# 07_LMS7002M_Power.net
KiCad netlist of a schematic drawn in Altium Designer
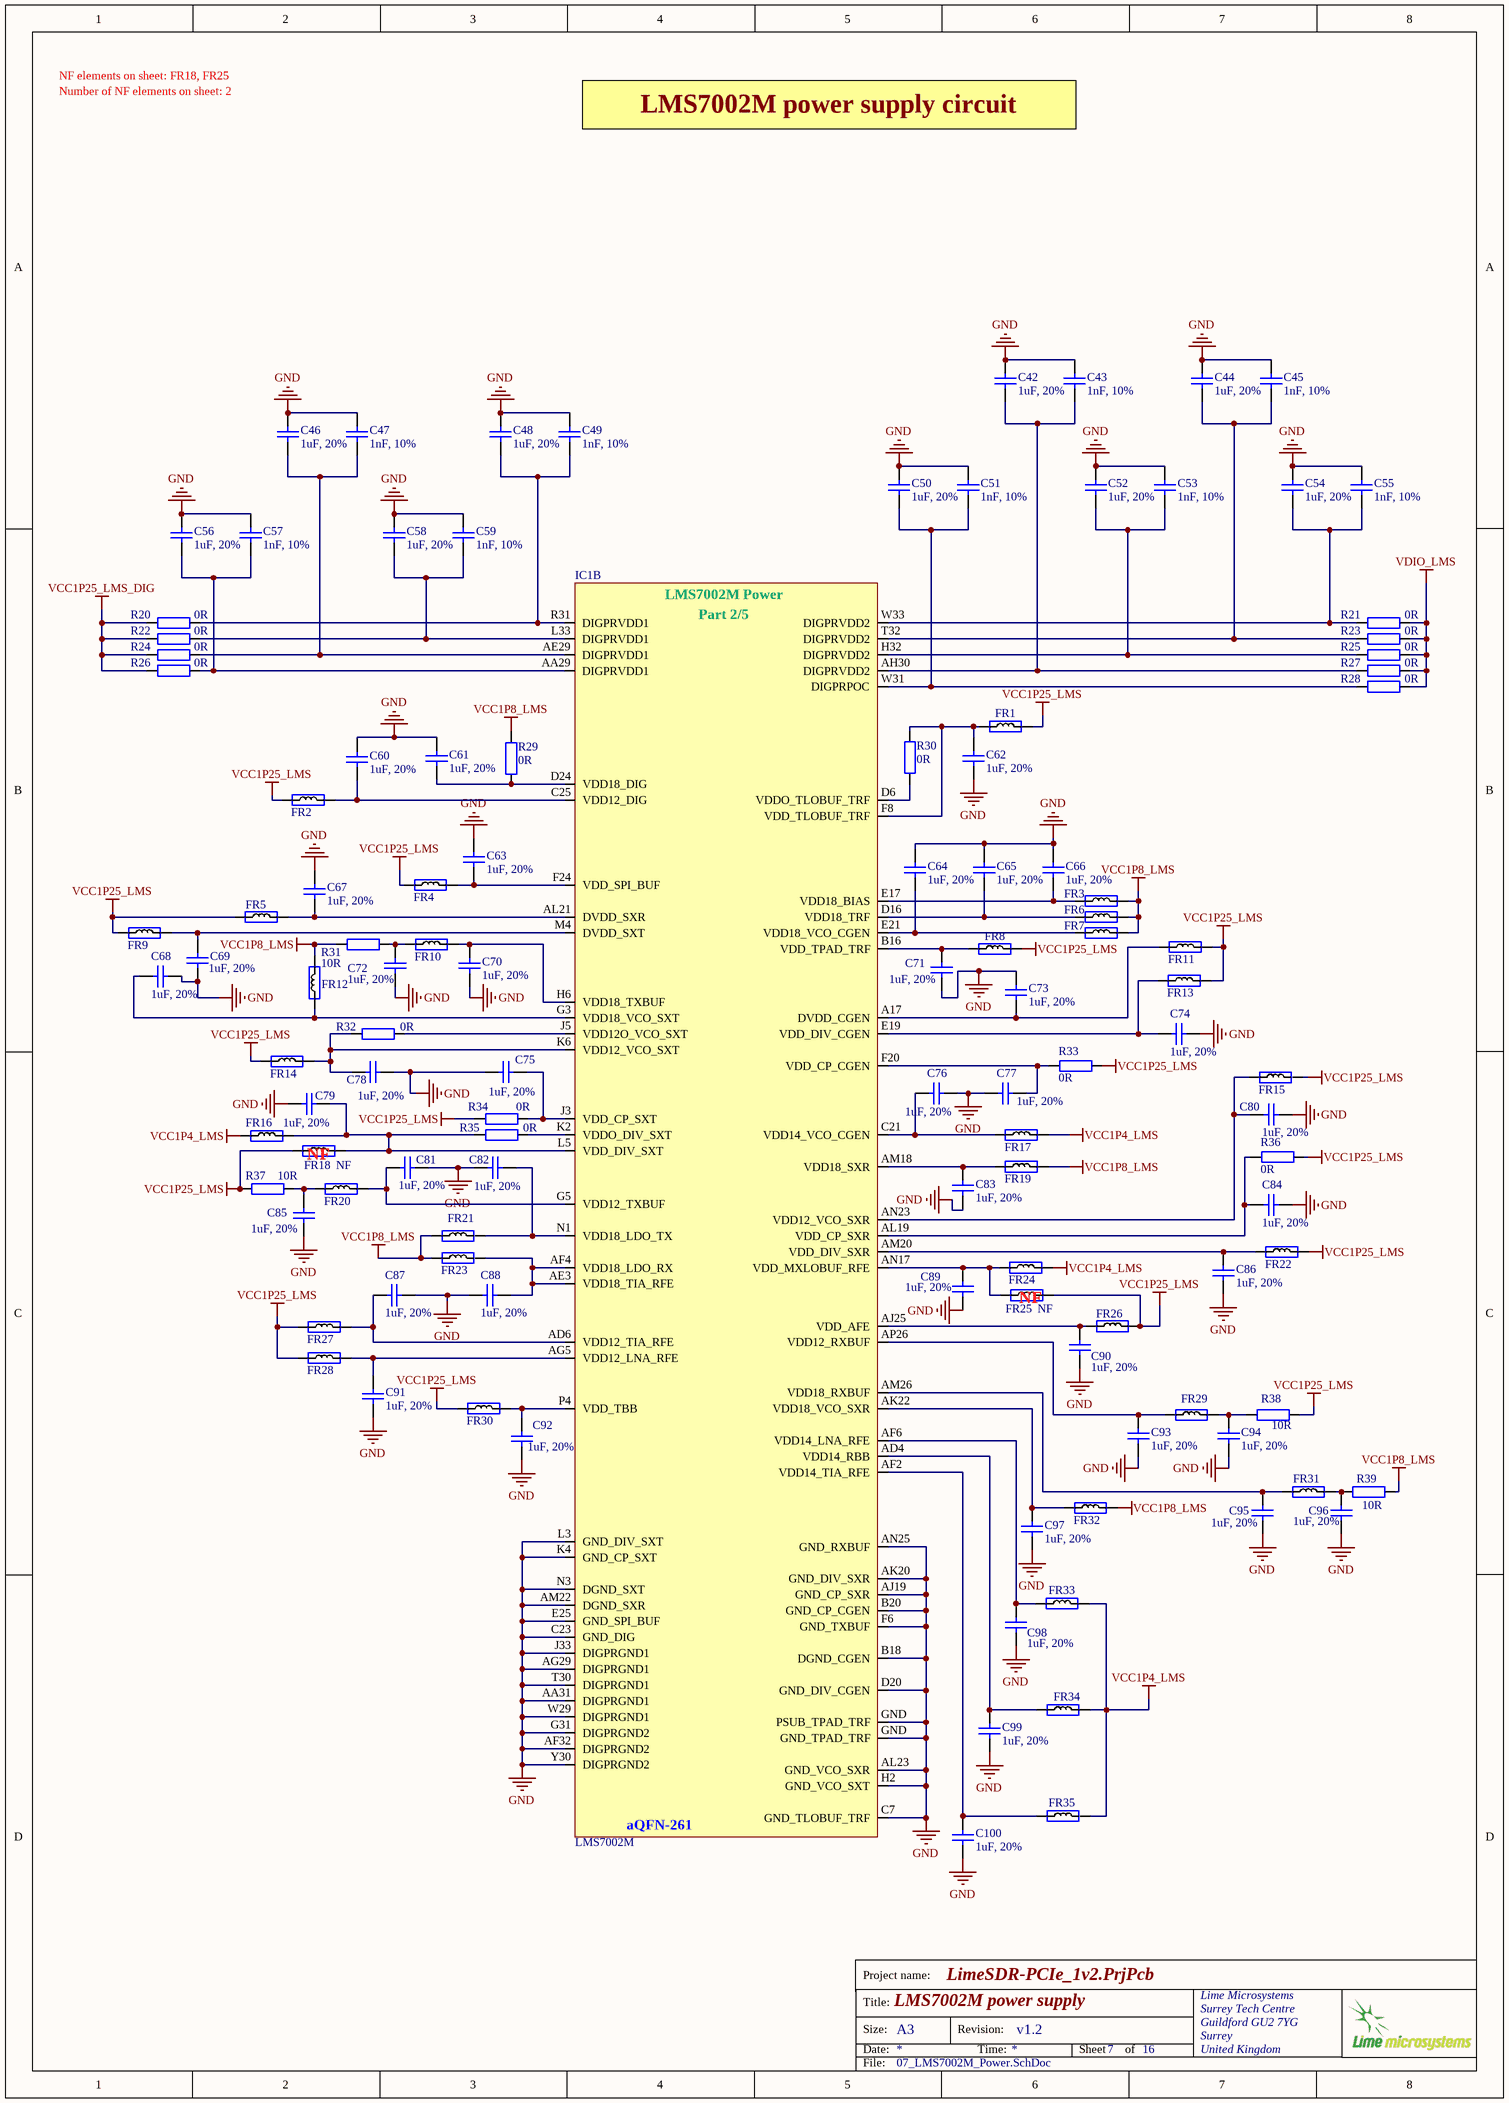
[diagram p0: 07_LMS7002M_Power.SchDoc]

(export (version "E")
  (design (tool "Eeschema 10.0.6"))
  (components
    (comp (ref "C42")
      (value "1uF, 20%")
      (footprint "CAP0201")
      (fields (field (name "TOLERANCE") "±20%") (field (name "MANUFACTURER") "TDK Corporation"))
      (libsource (lib "LimeMicroAltiumLib_schLib") (part "Cap_0402"))
    )
    (comp (ref "C43")
      (value "1nF, 10%")
      (footprint "CAP0201")
      (fields (field (name "TOLERANCE") "±10%") (field (name "MANUFACTURER") "TDK Corporation"))
      (libsource (lib "LimeMicroAltiumLib_schLib") (part "Cap_0402"))
    )
    (comp (ref "C44")
      (value "1uF, 20%")
      (footprint "CAP0201")
      (fields (field (name "TOLERANCE") "±20%") (field (name "MANUFACTURER") "TDK Corporation"))
      (libsource (lib "LimeMicroAltiumLib_schLib") (part "Cap_0402"))
    )
    (comp (ref "C45")
      (value "1nF, 10%")
      (footprint "CAP0201")
      (fields (field (name "TOLERANCE") "±10%") (field (name "MANUFACTURER") "TDK Corporation"))
      (libsource (lib "LimeMicroAltiumLib_schLib") (part "Cap_0402"))
    )
    (comp (ref "C46")
      (value "1uF, 20%")
      (footprint "CAP0201")
      (fields (field (name "TOLERANCE") "±20%") (field (name "MANUFACTURER") "TDK Corporation"))
      (libsource (lib "LimeMicroAltiumLib_schLib") (part "Cap_0402"))
    )
    (comp (ref "C47")
      (value "1nF, 10%")
      (footprint "CAP0201")
      (fields (field (name "TOLERANCE") "±10%") (field (name "MANUFACTURER") "TDK Corporation"))
      (libsource (lib "LimeMicroAltiumLib_schLib") (part "Cap_0402"))
    )
    (comp (ref "C48")
      (value "1uF, 20%")
      (footprint "CAP0201")
      (fields (field (name "TOLERANCE") "±20%") (field (name "MANUFACTURER") "TDK Corporation"))
      (libsource (lib "LimeMicroAltiumLib_schLib") (part "Cap_0402"))
    )
    (comp (ref "C49")
      (value "1nF, 10%")
      (footprint "CAP0201")
      (fields (field (name "TOLERANCE") "±10%") (field (name "MANUFACTURER") "TDK Corporation"))
      (libsource (lib "LimeMicroAltiumLib_schLib") (part "Cap_0402"))
    )
    (comp (ref "C50")
      (value "1uF, 20%")
      (footprint "CAP0201")
      (fields (field (name "TOLERANCE") "±20%") (field (name "MANUFACTURER") "TDK Corporation"))
      (libsource (lib "LimeMicroAltiumLib_schLib") (part "Cap_0402"))
    )
    (comp (ref "C51")
      (value "1nF, 10%")
      (footprint "CAP0201")
      (fields (field (name "TOLERANCE") "±10%") (field (name "MANUFACTURER") "TDK Corporation"))
      (libsource (lib "LimeMicroAltiumLib_schLib") (part "Cap_0402"))
    )
    (comp (ref "C52")
      (value "1uF, 20%")
      (footprint "CAP0201")
      (fields (field (name "TOLERANCE") "±20%") (field (name "MANUFACTURER") "TDK Corporation"))
      (libsource (lib "LimeMicroAltiumLib_schLib") (part "Cap_0402"))
    )
    (comp (ref "C53")
      (value "1nF, 10%")
      (footprint "CAP0201")
      (fields (field (name "TOLERANCE") "±10%") (field (name "MANUFACTURER") "TDK Corporation"))
      (libsource (lib "LimeMicroAltiumLib_schLib") (part "Cap_0402"))
    )
    (comp (ref "C54")
      (value "1uF, 20%")
      (footprint "CAP0201")
      (fields (field (name "TOLERANCE") "±20%") (field (name "MANUFACTURER") "TDK Corporation"))
      (libsource (lib "LimeMicroAltiumLib_schLib") (part "Cap_0402"))
    )
    (comp (ref "C55")
      (value "1nF, 10%")
      (footprint "CAP0201")
      (fields (field (name "TOLERANCE") "±10%") (field (name "MANUFACTURER") "TDK Corporation"))
      (libsource (lib "LimeMicroAltiumLib_schLib") (part "Cap_0402"))
    )
    (comp (ref "C56")
      (value "1uF, 20%")
      (footprint "CAP0201")
      (fields (field (name "TOLERANCE") "±20%") (field (name "MANUFACTURER") "TDK Corporation"))
      (libsource (lib "LimeMicroAltiumLib_schLib") (part "Cap_0402"))
    )
    (comp (ref "C57")
      (value "1nF, 10%")
      (footprint "CAP0201")
      (fields (field (name "TOLERANCE") "±10%") (field (name "MANUFACTURER") "TDK Corporation"))
      (libsource (lib "LimeMicroAltiumLib_schLib") (part "Cap_0402"))
    )
    (comp (ref "C58")
      (value "1uF, 20%")
      (footprint "CAP0201")
      (fields (field (name "TOLERANCE") "±20%") (field (name "MANUFACTURER") "TDK Corporation"))
      (libsource (lib "LimeMicroAltiumLib_schLib") (part "Cap_0402"))
    )
    (comp (ref "C59")
      (value "1nF, 10%")
      (footprint "CAP0201")
      (fields (field (name "TOLERANCE") "±10%") (field (name "MANUFACTURER") "TDK Corporation"))
      (libsource (lib "LimeMicroAltiumLib_schLib") (part "Cap_0402"))
    )
    (comp (ref "C60")
      (value "1uF, 20%")
      (footprint "CAP0201")
      (fields (field (name "TOLERANCE") "±20%") (field (name "MANUFACTURER") "TDK Corporation"))
      (libsource (lib "LimeMicroAltiumLib_schLib") (part "Cap_0402"))
    )
    (comp (ref "C61")
      (value "1uF, 20%")
      (footprint "CAP0201")
      (fields (field (name "TOLERANCE") "±20%") (field (name "MANUFACTURER") "TDK Corporation"))
      (libsource (lib "LimeMicroAltiumLib_schLib") (part "Cap_0402"))
    )
    (comp (ref "C62")
      (value "1uF, 20%")
      (footprint "CAP0201")
      (fields (field (name "TOLERANCE") "±20%") (field (name "MANUFACTURER") "TDK Corporation"))
      (libsource (lib "LimeMicroAltiumLib_schLib") (part "Cap_0402"))
    )
    (comp (ref "C63")
      (value "1uF, 20%")
      (footprint "CAP0201")
      (fields (field (name "TOLERANCE") "±20%") (field (name "MANUFACTURER") "TDK Corporation"))
      (libsource (lib "LimeMicroAltiumLib_schLib") (part "Cap_0402"))
    )
    (comp (ref "C64")
      (value "1uF, 20%")
      (footprint "CAP0201")
      (fields (field (name "TOLERANCE") "±20%") (field (name "MANUFACTURER") "TDK Corporation"))
      (libsource (lib "LimeMicroAltiumLib_schLib") (part "Cap_0402"))
    )
    (comp (ref "C65")
      (value "1uF, 20%")
      (footprint "CAP0201")
      (fields (field (name "TOLERANCE") "±20%") (field (name "MANUFACTURER") "TDK Corporation"))
      (libsource (lib "LimeMicroAltiumLib_schLib") (part "Cap_0402"))
    )
    (comp (ref "C66")
      (value "1uF, 20%")
      (footprint "CAP0201")
      (fields (field (name "TOLERANCE") "±20%") (field (name "MANUFACTURER") "TDK Corporation"))
      (libsource (lib "LimeMicroAltiumLib_schLib") (part "Cap_0402"))
    )
    (comp (ref "C67")
      (value "1uF, 20%")
      (footprint "CAP0201")
      (fields (field (name "TOLERANCE") "±20%") (field (name "MANUFACTURER") "TDK Corporation"))
      (libsource (lib "LimeMicroAltiumLib_schLib") (part "Cap_0402"))
    )
    (comp (ref "C68")
      (value "1uF, 20%")
      (footprint "CAP0201")
      (fields (field (name "TOLERANCE") "±20%") (field (name "MANUFACTURER") "TDK Corporation"))
      (libsource (lib "LimeMicroAltiumLib_schLib") (part "Cap_0402"))
    )
    (comp (ref "C69")
      (value "1uF, 20%")
      (footprint "CAP0201")
      (fields (field (name "TOLERANCE") "±20%") (field (name "MANUFACTURER") "TDK Corporation"))
      (libsource (lib "LimeMicroAltiumLib_schLib") (part "Cap_0402"))
    )
    (comp (ref "C70")
      (value "1uF, 20%")
      (footprint "CAP0201")
      (fields (field (name "TOLERANCE") "±20%") (field (name "MANUFACTURER") "TDK Corporation"))
      (libsource (lib "LimeMicroAltiumLib_schLib") (part "Cap_0402"))
    )
    (comp (ref "C71")
      (value "1uF, 20%")
      (footprint "CAP0201")
      (fields (field (name "TOLERANCE") "±20%") (field (name "MANUFACTURER") "TDK Corporation"))
      (libsource (lib "LimeMicroAltiumLib_schLib") (part "Cap_0402"))
    )
    (comp (ref "C72")
      (value "1uF, 20%")
      (footprint "CAP0201")
      (fields (field (name "TOLERANCE") "±20%") (field (name "MANUFACTURER") "TDK Corporation"))
      (libsource (lib "LimeMicroAltiumLib_schLib") (part "Cap_0402"))
    )
    (comp (ref "C73")
      (value "1uF, 20%")
      (footprint "CAP0201")
      (fields (field (name "TOLERANCE") "±20%") (field (name "MANUFACTURER") "TDK Corporation"))
      (libsource (lib "LimeMicroAltiumLib_schLib") (part "Cap_0402"))
    )
    (comp (ref "C74")
      (value "1uF, 20%")
      (footprint "CAP0201")
      (fields (field (name "TOLERANCE") "±20%") (field (name "MANUFACTURER") "TDK Corporation"))
      (libsource (lib "LimeMicroAltiumLib_schLib") (part "Cap_0402"))
    )
    (comp (ref "C75")
      (value "1uF, 20%")
      (footprint "CAP0201")
      (fields (field (name "TOLERANCE") "±20%") (field (name "MANUFACTURER") "TDK Corporation"))
      (libsource (lib "LimeMicroAltiumLib_schLib") (part "Cap_0402"))
    )
    (comp (ref "C76")
      (value "1uF, 20%")
      (footprint "CAP0201")
      (fields (field (name "TOLERANCE") "±20%") (field (name "MANUFACTURER") "TDK Corporation"))
      (libsource (lib "LimeMicroAltiumLib_schLib") (part "Cap_0402"))
    )
    (comp (ref "C77")
      (value "1uF, 20%")
      (footprint "CAP0201")
      (fields (field (name "TOLERANCE") "±20%") (field (name "MANUFACTURER") "TDK Corporation"))
      (libsource (lib "LimeMicroAltiumLib_schLib") (part "Cap_0402"))
    )
    (comp (ref "C78")
      (value "1uF, 20%")
      (footprint "CAP0201")
      (fields (field (name "TOLERANCE") "±20%") (field (name "MANUFACTURER") "TDK Corporation"))
      (libsource (lib "LimeMicroAltiumLib_schLib") (part "Cap_0402"))
    )
    (comp (ref "C79")
      (value "1uF, 20%")
      (footprint "CAP0201")
      (fields (field (name "TOLERANCE") "±20%") (field (name "MANUFACTURER") "TDK Corporation"))
      (libsource (lib "LimeMicroAltiumLib_schLib") (part "Cap_0402"))
    )
    (comp (ref "C80")
      (value "1uF, 20%")
      (footprint "CAP0201")
      (fields (field (name "TOLERANCE") "±20%") (field (name "MANUFACTURER") "TDK Corporation"))
      (libsource (lib "LimeMicroAltiumLib_schLib") (part "Cap_0402"))
    )
    (comp (ref "C81")
      (value "1uF, 20%")
      (footprint "CAP0201")
      (fields (field (name "TOLERANCE") "±20%") (field (name "MANUFACTURER") "TDK Corporation"))
      (libsource (lib "LimeMicroAltiumLib_schLib") (part "Cap_0402"))
    )
    (comp (ref "C82")
      (value "1uF, 20%")
      (footprint "CAP0201")
      (fields (field (name "TOLERANCE") "±20%") (field (name "MANUFACTURER") "TDK Corporation"))
      (libsource (lib "LimeMicroAltiumLib_schLib") (part "Cap_0402"))
    )
    (comp (ref "C83")
      (value "1uF, 20%")
      (footprint "CAP0201")
      (fields (field (name "TOLERANCE") "±20%") (field (name "MANUFACTURER") "TDK Corporation"))
      (libsource (lib "LimeMicroAltiumLib_schLib") (part "Cap_0402"))
    )
    (comp (ref "C84")
      (value "1uF, 20%")
      (footprint "CAP0201")
      (fields (field (name "TOLERANCE") "±20%") (field (name "MANUFACTURER") "TDK Corporation"))
      (libsource (lib "LimeMicroAltiumLib_schLib") (part "Cap_0402"))
    )
    (comp (ref "C85")
      (value "1uF, 20%")
      (footprint "CAP0201")
      (fields (field (name "TOLERANCE") "±20%") (field (name "MANUFACTURER") "TDK Corporation"))
      (libsource (lib "LimeMicroAltiumLib_schLib") (part "Cap_0402"))
    )
    (comp (ref "C86")
      (value "1uF, 20%")
      (footprint "CAP0201")
      (fields (field (name "TOLERANCE") "±20%") (field (name "MANUFACTURER") "TDK Corporation"))
      (libsource (lib "LimeMicroAltiumLib_schLib") (part "Cap_0402"))
    )
    (comp (ref "C87")
      (value "1uF, 20%")
      (footprint "CAP0201")
      (fields (field (name "TOLERANCE") "±20%") (field (name "MANUFACTURER") "TDK Corporation"))
      (libsource (lib "LimeMicroAltiumLib_schLib") (part "Cap_0402"))
    )
    (comp (ref "C88")
      (value "1uF, 20%")
      (footprint "CAP0201")
      (fields (field (name "TOLERANCE") "±20%") (field (name "MANUFACTURER") "TDK Corporation"))
      (libsource (lib "LimeMicroAltiumLib_schLib") (part "Cap_0402"))
    )
    (comp (ref "C89")
      (value "1uF, 20%")
      (footprint "CAP0201")
      (fields (field (name "TOLERANCE") "±20%") (field (name "MANUFACTURER") "TDK Corporation"))
      (libsource (lib "LimeMicroAltiumLib_schLib") (part "Cap_0402"))
    )
    (comp (ref "C90")
      (value "1uF, 20%")
      (footprint "CAP0201")
      (fields (field (name "TOLERANCE") "±20%") (field (name "MANUFACTURER") "TDK Corporation"))
      (libsource (lib "LimeMicroAltiumLib_schLib") (part "Cap_0402"))
    )
    (comp (ref "C91")
      (value "1uF, 20%")
      (footprint "CAP0201")
      (fields (field (name "TOLERANCE") "±20%") (field (name "MANUFACTURER") "TDK Corporation"))
      (libsource (lib "LimeMicroAltiumLib_schLib") (part "Cap_0402"))
    )
    (comp (ref "C92")
      (value "1uF, 20%")
      (footprint "CAP0201")
      (fields (field (name "TOLERANCE") "±20%") (field (name "MANUFACTURER") "TDK Corporation"))
      (libsource (lib "LimeMicroAltiumLib_schLib") (part "Cap_0402"))
    )
    (comp (ref "C93")
      (value "1uF, 20%")
      (footprint "CAP0201")
      (fields (field (name "TOLERANCE") "±20%") (field (name "MANUFACTURER") "TDK Corporation"))
      (libsource (lib "LimeMicroAltiumLib_schLib") (part "Cap_0402"))
    )
    (comp (ref "C94")
      (value "1uF, 20%")
      (footprint "CAP0201")
      (fields (field (name "TOLERANCE") "±20%") (field (name "MANUFACTURER") "TDK Corporation"))
      (libsource (lib "LimeMicroAltiumLib_schLib") (part "Cap_0402"))
    )
    (comp (ref "C95")
      (value "1uF, 20%")
      (footprint "CAP0201")
      (fields (field (name "TOLERANCE") "±20%") (field (name "MANUFACTURER") "TDK Corporation"))
      (libsource (lib "LimeMicroAltiumLib_schLib") (part "Cap_0402"))
    )
    (comp (ref "C96")
      (value "1uF, 20%")
      (footprint "CAP0201")
      (fields (field (name "TOLERANCE") "±20%") (field (name "MANUFACTURER") "TDK Corporation"))
      (libsource (lib "LimeMicroAltiumLib_schLib") (part "Cap_0402"))
    )
    (comp (ref "C97")
      (value "1uF, 20%")
      (footprint "CAP0201")
      (fields (field (name "TOLERANCE") "±20%") (field (name "MANUFACTURER") "TDK Corporation"))
      (libsource (lib "LimeMicroAltiumLib_schLib") (part "Cap_0402"))
    )
    (comp (ref "C98")
      (value "1uF, 20%")
      (footprint "CAP0201")
      (fields (field (name "TOLERANCE") "±20%") (field (name "MANUFACTURER") "TDK Corporation"))
      (libsource (lib "LimeMicroAltiumLib_schLib") (part "Cap_0402"))
    )
    (comp (ref "C99")
      (value "1uF, 20%")
      (footprint "CAP0201")
      (fields (field (name "TOLERANCE") "±20%") (field (name "MANUFACTURER") "TDK Corporation"))
      (libsource (lib "LimeMicroAltiumLib_schLib") (part "Cap_0402"))
    )
    (comp (ref "C100")
      (value "1uF, 20%")
      (footprint "CAP0201")
      (fields (field (name "TOLERANCE") "±20%") (field (name "MANUFACTURER") "TDK Corporation"))
      (libsource (lib "LimeMicroAltiumLib_schLib") (part "Cap_0402"))
    )
    (comp (ref "FR1")
      (value "600R, 0.27A")
      (footprint "RES0201")
      (fields (field (name "MANUFACTURER") "Taiyo Yuden"))
      (libsource (lib "LimeMicroAltiumLib_schLib") (part "Ferrite"))
    )
    (comp (ref "FR2")
      (value "600R, 0.27A")
      (footprint "RES0201")
      (fields (field (name "MANUFACTURER") "Taiyo Yuden"))
      (libsource (lib "LimeMicroAltiumLib_schLib") (part "Ferrite"))
    )
    (comp (ref "FR3")
      (value "600R, 0.27A")
      (footprint "RES0201")
      (fields (field (name "MANUFACTURER") "Taiyo Yuden"))
      (libsource (lib "LimeMicroAltiumLib_schLib") (part "Ferrite"))
    )
    (comp (ref "FR4")
      (value "600R, 0.27A")
      (footprint "RES0201")
      (fields (field (name "MANUFACTURER") "Taiyo Yuden"))
      (libsource (lib "LimeMicroAltiumLib_schLib") (part "Ferrite"))
    )
    (comp (ref "FR5")
      (value "600R, 0.27A")
      (footprint "RES0201")
      (fields (field (name "MANUFACTURER") "Taiyo Yuden"))
      (libsource (lib "LimeMicroAltiumLib_schLib") (part "Ferrite"))
    )
    (comp (ref "FR6")
      (value "600R, 0.27A")
      (footprint "RES0201")
      (fields (field (name "MANUFACTURER") "Taiyo Yuden"))
      (libsource (lib "LimeMicroAltiumLib_schLib") (part "Ferrite"))
    )
    (comp (ref "FR7")
      (value "600R, 0.27A")
      (footprint "RES0201")
      (fields (field (name "MANUFACTURER") "Taiyo Yuden"))
      (libsource (lib "LimeMicroAltiumLib_schLib") (part "Ferrite"))
    )
    (comp (ref "FR8")
      (value "600R, 0.27A")
      (footprint "RES0201")
      (fields (field (name "MANUFACTURER") "Taiyo Yuden"))
      (libsource (lib "LimeMicroAltiumLib_schLib") (part "Ferrite"))
    )
    (comp (ref "FR9")
      (value "600R, 0.27A")
      (footprint "RES0201")
      (fields (field (name "MANUFACTURER") "Taiyo Yuden"))
      (libsource (lib "LimeMicroAltiumLib_schLib") (part "Ferrite"))
    )
    (comp (ref "FR10")
      (value "600R, 0.27A")
      (footprint "RES0201")
      (fields (field (name "MANUFACTURER") "Taiyo Yuden"))
      (libsource (lib "LimeMicroAltiumLib_schLib") (part "Ferrite"))
    )
    (comp (ref "FR11")
      (value "600R, 0.27A")
      (footprint "RES0201")
      (fields (field (name "MANUFACTURER") "Taiyo Yuden"))
      (libsource (lib "LimeMicroAltiumLib_schLib") (part "Ferrite"))
    )
    (comp (ref "FR12")
      (value "600R, 0.27A")
      (footprint "RES0201")
      (fields (field (name "MANUFACTURER") "Taiyo Yuden"))
      (libsource (lib "LimeMicroAltiumLib_schLib") (part "Ferrite"))
    )
    (comp (ref "FR13")
      (value "600R, 0.27A")
      (footprint "RES0201")
      (fields (field (name "MANUFACTURER") "Taiyo Yuden"))
      (libsource (lib "LimeMicroAltiumLib_schLib") (part "Ferrite"))
    )
    (comp (ref "FR14")
      (value "600R, 0.27A")
      (footprint "RES0201")
      (fields (field (name "MANUFACTURER") "Taiyo Yuden"))
      (libsource (lib "LimeMicroAltiumLib_schLib") (part "Ferrite"))
    )
    (comp (ref "FR15")
      (value "600R, 0.27A")
      (footprint "RES0201")
      (fields (field (name "MANUFACTURER") "Taiyo Yuden"))
      (libsource (lib "LimeMicroAltiumLib_schLib") (part "Ferrite"))
    )
    (comp (ref "FR16")
      (value "600R, 0.27A")
      (footprint "RES0201")
      (fields (field (name "MANUFACTURER") "Taiyo Yuden"))
      (libsource (lib "LimeMicroAltiumLib_schLib") (part "Ferrite"))
    )
    (comp (ref "FR17")
      (value "600R, 0.27A")
      (footprint "RES0201")
      (fields (field (name "MANUFACTURER") "Taiyo Yuden"))
      (libsource (lib "LimeMicroAltiumLib_schLib") (part "Ferrite"))
    )
    (comp (ref "FR18")
      (value "600R, 0.27A")
      (footprint "RES0201")
      (fields (field (name "MANUFACTURER") "Taiyo Yuden") (field (name "ASSEMBLY INFO") "NF"))
      (libsource (lib "LimeMicroAltiumLib_schLib") (part "Ferrite"))
    )
    (comp (ref "FR19")
      (value "600R, 0.27A")
      (footprint "RES0201")
      (fields (field (name "MANUFACTURER") "Taiyo Yuden"))
      (libsource (lib "LimeMicroAltiumLib_schLib") (part "Ferrite"))
    )
    (comp (ref "FR20")
      (value "600R, 0.27A")
      (footprint "RES0201")
      (fields (field (name "MANUFACTURER") "Taiyo Yuden"))
      (libsource (lib "LimeMicroAltiumLib_schLib") (part "Ferrite"))
    )
    (comp (ref "FR21")
      (value "600R, 0.27A")
      (footprint "RES0201")
      (fields (field (name "MANUFACTURER") "Taiyo Yuden"))
      (libsource (lib "LimeMicroAltiumLib_schLib") (part "Ferrite"))
    )
    (comp (ref "FR22")
      (value "600R, 0.27A")
      (footprint "RES0201")
      (fields (field (name "MANUFACTURER") "Taiyo Yuden"))
      (libsource (lib "LimeMicroAltiumLib_schLib") (part "Ferrite"))
    )
    (comp (ref "FR23")
      (value "600R, 0.27A")
      (footprint "RES0201")
      (fields (field (name "MANUFACTURER") "Taiyo Yuden"))
      (libsource (lib "LimeMicroAltiumLib_schLib") (part "Ferrite"))
    )
    (comp (ref "FR24")
      (value "600R, 0.27A")
      (footprint "RES0201")
      (fields (field (name "MANUFACTURER") "Taiyo Yuden"))
      (libsource (lib "LimeMicroAltiumLib_schLib") (part "Ferrite"))
    )
    (comp (ref "FR25")
      (value "600R, 0.27A")
      (footprint "RES0201")
      (fields (field (name "MANUFACTURER") "Taiyo Yuden") (field (name "ASSEMBLY INFO") "NF"))
      (libsource (lib "LimeMicroAltiumLib_schLib") (part "Ferrite"))
    )
    (comp (ref "FR26")
      (value "600R, 0.27A")
      (footprint "RES0201")
      (fields (field (name "MANUFACTURER") "Taiyo Yuden"))
      (libsource (lib "LimeMicroAltiumLib_schLib") (part "Ferrite"))
    )
    (comp (ref "FR27")
      (value "600R, 0.27A")
      (footprint "RES0201")
      (fields (field (name "MANUFACTURER") "Taiyo Yuden"))
      (libsource (lib "LimeMicroAltiumLib_schLib") (part "Ferrite"))
    )
    (comp (ref "FR28")
      (value "600R, 0.27A")
      (footprint "RES0201")
      (fields (field (name "MANUFACTURER") "Taiyo Yuden"))
      (libsource (lib "LimeMicroAltiumLib_schLib") (part "Ferrite"))
    )
    (comp (ref "FR29")
      (value "600R, 0.27A")
      (footprint "RES0201")
      (fields (field (name "MANUFACTURER") "Taiyo Yuden"))
      (libsource (lib "LimeMicroAltiumLib_schLib") (part "Ferrite"))
    )
    (comp (ref "FR30")
      (value "600R, 0.27A")
      (footprint "RES0201")
      (fields (field (name "MANUFACTURER") "Taiyo Yuden"))
      (libsource (lib "LimeMicroAltiumLib_schLib") (part "Ferrite"))
    )
    (comp (ref "FR31")
      (value "600R, 0.27A")
      (footprint "RES0201")
      (fields (field (name "MANUFACTURER") "Taiyo Yuden"))
      (libsource (lib "LimeMicroAltiumLib_schLib") (part "Ferrite"))
    )
    (comp (ref "FR32")
      (value "600R, 0.27A")
      (footprint "RES0201")
      (fields (field (name "MANUFACTURER") "Taiyo Yuden"))
      (libsource (lib "LimeMicroAltiumLib_schLib") (part "Ferrite"))
    )
    (comp (ref "FR33")
      (value "600R, 0.27A")
      (footprint "RES0201")
      (fields (field (name "MANUFACTURER") "Taiyo Yuden"))
      (libsource (lib "LimeMicroAltiumLib_schLib") (part "Ferrite"))
    )
    (comp (ref "FR34")
      (value "600R, 0.27A")
      (footprint "RES0201")
      (fields (field (name "MANUFACTURER") "Taiyo Yuden"))
      (libsource (lib "LimeMicroAltiumLib_schLib") (part "Ferrite"))
    )
    (comp (ref "FR35")
      (value "600R, 0.27A")
      (footprint "RES0201")
      (fields (field (name "MANUFACTURER") "Taiyo Yuden"))
      (libsource (lib "LimeMicroAltiumLib_schLib") (part "Ferrite"))
    )
    (comp (ref "IC1")
      (value "LMS7002M")
      (footprint "LMS7002M_v2")
      (fields (field (name "MANUFACTURER") "Lime Microsystems"))
      (libsource (lib "LimeMicroAltiumLib_schLib") (part "LMS7002M"))
    )
    (comp (ref "R20")
      (value "0R")
      (footprint "RES0402")
      (fields (field (name "MANUFACTURER") "Yageo") (field (name "TOLERANCE") "Jumper"))
      (libsource (lib "LimeMicroAltiumLib_schLib") (part "Res_0402"))
    )
    (comp (ref "R21")
      (value "0R")
      (footprint "RES0402")
      (fields (field (name "MANUFACTURER") "Yageo") (field (name "TOLERANCE") "Jumper"))
      (libsource (lib "LimeMicroAltiumLib_schLib") (part "Res_0402"))
    )
    (comp (ref "R22")
      (value "0R")
      (footprint "RES0402")
      (fields (field (name "MANUFACTURER") "Yageo") (field (name "TOLERANCE") "Jumper"))
      (libsource (lib "LimeMicroAltiumLib_schLib") (part "Res_0402"))
    )
    (comp (ref "R23")
      (value "0R")
      (footprint "RES0402")
      (fields (field (name "MANUFACTURER") "Yageo") (field (name "TOLERANCE") "Jumper"))
      (libsource (lib "LimeMicroAltiumLib_schLib") (part "Res_0402"))
    )
    (comp (ref "R24")
      (value "0R")
      (footprint "RES0402")
      (fields (field (name "MANUFACTURER") "Yageo") (field (name "TOLERANCE") "Jumper"))
      (libsource (lib "LimeMicroAltiumLib_schLib") (part "Res_0402"))
    )
    (comp (ref "R25")
      (value "0R")
      (footprint "RES0402")
      (fields (field (name "MANUFACTURER") "Yageo") (field (name "TOLERANCE") "Jumper"))
      (libsource (lib "LimeMicroAltiumLib_schLib") (part "Res_0402"))
    )
    (comp (ref "R26")
      (value "0R")
      (footprint "RES0402")
      (fields (field (name "MANUFACTURER") "Yageo") (field (name "TOLERANCE") "Jumper"))
      (libsource (lib "LimeMicroAltiumLib_schLib") (part "Res_0402"))
    )
    (comp (ref "R27")
      (value "0R")
      (footprint "RES0402")
      (fields (field (name "MANUFACTURER") "Yageo") (field (name "TOLERANCE") "Jumper"))
      (libsource (lib "LimeMicroAltiumLib_schLib") (part "Res_0402"))
    )
    (comp (ref "R28")
      (value "0R")
      (footprint "RES0402")
      (fields (field (name "MANUFACTURER") "Yageo") (field (name "TOLERANCE") "Jumper"))
      (libsource (lib "LimeMicroAltiumLib_schLib") (part "Res_0402"))
    )
    (comp (ref "R29")
      (value "0R")
      (footprint "RES0201")
      (fields (field (name "MANUFACTURER") "Rohm Semiconductor") (field (name "TOLERANCE") "Jumper"))
      (libsource (lib "LimeMicroAltiumLib_schLib") (part "Res_0402"))
    )
    (comp (ref "R30")
      (value "0R")
      (footprint "RES0201")
      (fields (field (name "MANUFACTURER") "Rohm Semiconductor") (field (name "TOLERANCE") "Jumper"))
      (libsource (lib "LimeMicroAltiumLib_schLib") (part "Res_0402"))
    )
    (comp (ref "R31")
      (value "10R")
      (footprint "RES0201")
      (fields
        (field (name "MANUFACTURER") "Panasonic Electronic Components")
        (field (name "TOLERANCE") "±1%")
        (field (name "MANUFACTURER PART NUMBER") "ERJ-1GEF10R0C")
      )
      (libsource (lib "LimeMicroAltiumLib_schLib") (part "Res_0402"))
    )
    (comp (ref "R32")
      (value "0R")
      (footprint "RES0201")
      (fields (field (name "MANUFACTURER") "Rohm Semiconductor") (field (name "TOLERANCE") "Jumper"))
      (libsource (lib "LimeMicroAltiumLib_schLib") (part "Res_0402"))
    )
    (comp (ref "R33")
      (value "0R")
      (footprint "RES0201")
      (fields (field (name "MANUFACTURER") "Rohm Semiconductor") (field (name "TOLERANCE") "Jumper"))
      (libsource (lib "LimeMicroAltiumLib_schLib") (part "Res_0402"))
    )
    (comp (ref "R34")
      (value "0R")
      (footprint "RES0201")
      (fields (field (name "MANUFACTURER") "Rohm Semiconductor") (field (name "TOLERANCE") "Jumper"))
      (libsource (lib "LimeMicroAltiumLib_schLib") (part "Res_0402"))
    )
    (comp (ref "R35")
      (value "0R")
      (footprint "RES0201")
      (fields (field (name "MANUFACTURER") "Rohm Semiconductor") (field (name "TOLERANCE") "Jumper"))
      (libsource (lib "LimeMicroAltiumLib_schLib") (part "Res_0402"))
    )
    (comp (ref "R36")
      (value "0R")
      (footprint "RES0201")
      (fields (field (name "MANUFACTURER") "Rohm Semiconductor") (field (name "TOLERANCE") "Jumper"))
      (libsource (lib "LimeMicroAltiumLib_schLib") (part "Res_0402"))
    )
    (comp (ref "R37")
      (value "10R")
      (footprint "RES0201")
      (fields
        (field (name "MANUFACTURER") "Panasonic Electronic Components")
        (field (name "TOLERANCE") "±1%")
        (field (name "MANUFACTURER PART NUMBER") "ERJ-1GEF10R0C")
      )
      (libsource (lib "LimeMicroAltiumLib_schLib") (part "Res_0402"))
    )
    (comp (ref "R38")
      (value "10R")
      (footprint "RES0201")
      (fields
        (field (name "MANUFACTURER") "Panasonic Electronic Components")
        (field (name "TOLERANCE") "±1%")
        (field (name "MANUFACTURER PART NUMBER") "ERJ-1GEF10R0C")
      )
      (libsource (lib "LimeMicroAltiumLib_schLib") (part "Res_0402"))
    )
    (comp (ref "R39")
      (value "10R")
      (footprint "RES0201")
      (fields
        (field (name "MANUFACTURER") "Panasonic Electronic Components")
        (field (name "TOLERANCE") "±1%")
        (field (name "MANUFACTURER PART NUMBER") "ERJ-1GEF10R0C")
      )
      (libsource (lib "LimeMicroAltiumLib_schLib") (part "Res_0402"))
    )
  )
  (nets
    (net (code "1") (name "GND") (class "Default")
      (node (ref "C100") (pin "2") (pinfunction "2_2") (pintype "passive"))
      (node (ref "C42") (pin "2") (pinfunction "2_2") (pintype "passive"))
      (node (ref "C43") (pin "2") (pinfunction "2_2") (pintype "passive"))
      (node (ref "C44") (pin "2") (pinfunction "2_2") (pintype "passive"))
      (node (ref "C45") (pin "2") (pinfunction "2_2") (pintype "passive"))
      (node (ref "C46") (pin "2") (pinfunction "2_2") (pintype "passive"))
      (node (ref "C47") (pin "2") (pinfunction "2_2") (pintype "passive"))
      (node (ref "C48") (pin "2") (pinfunction "2_2") (pintype "passive"))
      (node (ref "C49") (pin "2") (pinfunction "2_2") (pintype "passive"))
      (node (ref "C50") (pin "2") (pinfunction "2_2") (pintype "passive"))
      (node (ref "C51") (pin "2") (pinfunction "2_2") (pintype "passive"))
      (node (ref "C52") (pin "2") (pinfunction "2_2") (pintype "passive"))
      (node (ref "C53") (pin "2") (pinfunction "2_2") (pintype "passive"))
      (node (ref "C54") (pin "2") (pinfunction "2_2") (pintype "passive"))
      (node (ref "C55") (pin "2") (pinfunction "2_2") (pintype "passive"))
      (node (ref "C56") (pin "2") (pinfunction "2_2") (pintype "passive"))
      (node (ref "C57") (pin "2") (pinfunction "2_2") (pintype "passive"))
      (node (ref "C58") (pin "2") (pinfunction "2_2") (pintype "passive"))
      (node (ref "C59") (pin "2") (pinfunction "2_2") (pintype "passive"))
      (node (ref "C60") (pin "2") (pinfunction "2_2") (pintype "passive"))
      (node (ref "C61") (pin "2") (pinfunction "2_2") (pintype "passive"))
      (node (ref "C62") (pin "2") (pinfunction "2_2") (pintype "passive"))
      (node (ref "C63") (pin "2") (pinfunction "2_2") (pintype "passive"))
      (node (ref "C64") (pin "2") (pinfunction "2_2") (pintype "passive"))
      (node (ref "C65") (pin "2") (pinfunction "2_2") (pintype "passive"))
      (node (ref "C66") (pin "2") (pinfunction "2_2") (pintype "passive"))
      (node (ref "C67") (pin "2") (pinfunction "2_2") (pintype "passive"))
      (node (ref "C68") (pin "2") (pinfunction "2_2") (pintype "passive"))
      (node (ref "C69") (pin "2") (pinfunction "2_2") (pintype "passive"))
      (node (ref "C70") (pin "2") (pinfunction "2_2") (pintype "passive"))
      (node (ref "C71") (pin "2") (pinfunction "2_2") (pintype "passive"))
      (node (ref "C72") (pin "2") (pinfunction "2_2") (pintype "passive"))
      (node (ref "C73") (pin "2") (pinfunction "2_2") (pintype "passive"))
      (node (ref "C74") (pin "2") (pinfunction "2_2") (pintype "passive"))
      (node (ref "C75") (pin "2") (pinfunction "2_2") (pintype "passive"))
      (node (ref "C76") (pin "2") (pinfunction "2_2") (pintype "passive"))
      (node (ref "C77") (pin "2") (pinfunction "2_2") (pintype "passive"))
      (node (ref "C78") (pin "1") (pinfunction "1_1") (pintype "passive"))
      (node (ref "C79") (pin "2") (pinfunction "2_2") (pintype "passive"))
      (node (ref "C80") (pin "2") (pinfunction "2_2") (pintype "passive"))
      (node (ref "C81") (pin "2") (pinfunction "2_2") (pintype "passive"))
      (node (ref "C82") (pin "2") (pinfunction "2_2") (pintype "passive"))
      (node (ref "C83") (pin "2") (pinfunction "2_2") (pintype "passive"))
      (node (ref "C84") (pin "2") (pinfunction "2_2") (pintype "passive"))
      (node (ref "C85") (pin "2") (pinfunction "2_2") (pintype "passive"))
      (node (ref "C86") (pin "2") (pinfunction "2_2") (pintype "passive"))
      (node (ref "C87") (pin "2") (pinfunction "2_2") (pintype "passive"))
      (node (ref "C88") (pin "2") (pinfunction "2_2") (pintype "passive"))
      (node (ref "C89") (pin "2") (pinfunction "2_2") (pintype "passive"))
      (node (ref "C90") (pin "2") (pinfunction "2_2") (pintype "passive"))
      (node (ref "C91") (pin "2") (pinfunction "2_2") (pintype "passive"))
      (node (ref "C92") (pin "2") (pinfunction "2_2") (pintype "passive"))
      (node (ref "C93") (pin "2") (pinfunction "2_2") (pintype "passive"))
      (node (ref "C94") (pin "2") (pinfunction "2_2") (pintype "passive"))
      (node (ref "C95") (pin "2") (pinfunction "2_2") (pintype "passive"))
      (node (ref "C96") (pin "2") (pinfunction "2_2") (pintype "passive"))
      (node (ref "C97") (pin "2") (pinfunction "2_2") (pintype "passive"))
      (node (ref "C98") (pin "2") (pinfunction "2_2") (pintype "passive"))
      (node (ref "C99") (pin "2") (pinfunction "2_2") (pintype "passive"))
      (node (ref "IC1") (pin "AA31") (pinfunction "DIGPRGND1_AA31") (pintype "passive"))
      (node (ref "IC1") (pin "AF32") (pinfunction "DIGPRGND2_AF32") (pintype "passive"))
      (node (ref "IC1") (pin "AG29") (pinfunction "DIGPRGND1_AG29") (pintype "passive"))
      (node (ref "IC1") (pin "AJ19") (pinfunction "GND_CP_SXR_AJ19") (pintype "passive"))
      (node (ref "IC1") (pin "AK20") (pinfunction "GND_DIV_SXR_AK20") (pintype "passive"))
      (node (ref "IC1") (pin "AL23") (pinfunction "GND_VCO_SXR_AL23") (pintype "passive"))
      (node (ref "IC1") (pin "AM22") (pinfunction "DGND_SXR_AM22") (pintype "passive"))
      (node (ref "IC1") (pin "AN25") (pinfunction "GND_RXBUF_AN25") (pintype "passive"))
      (node (ref "IC1") (pin "B18") (pinfunction "DGND_CGEN_B18") (pintype "passive"))
      (node (ref "IC1") (pin "B20") (pinfunction "GND_CP_CGEN_B20") (pintype "passive"))
      (node (ref "IC1") (pin "C23") (pinfunction "GND_DIG_C23") (pintype "passive"))
      (node (ref "IC1") (pin "C7") (pinfunction "GND_TLOBUF_TRF_C7") (pintype "passive"))
      (node (ref "IC1") (pin "D20") (pinfunction "GND_DIV_CGEN_D20") (pintype "passive"))
      (node (ref "IC1") (pin "E25") (pinfunction "GND_SPI_BUF_E25") (pintype "passive"))
      (node (ref "IC1") (pin "F6") (pinfunction "GND_TXBUF_F6") (pintype "passive"))
      (node (ref "IC1") (pin "G31") (pinfunction "DIGPRGND2_G31") (pintype "passive"))
      (node (ref "IC1") (pin "GND") (pinfunction "PSUB_TPAD_TRF_GND") (pintype "passive"))
      (node (ref "IC1") (pin "H2") (pinfunction "GND_VCO_SXT_H2") (pintype "passive"))
      (node (ref "IC1") (pin "J33") (pinfunction "DIGPRGND1_J33") (pintype "passive"))
      (node (ref "IC1") (pin "K4") (pinfunction "GND_CP_SXT_K4") (pintype "passive"))
      (node (ref "IC1") (pin "L3") (pinfunction "GND_DIV_SXT_L3") (pintype "passive"))
      (node (ref "IC1") (pin "N3") (pinfunction "DGND_SXT_N3") (pintype "passive"))
      (node (ref "IC1") (pin "T30") (pinfunction "DIGPRGND1_T30") (pintype "passive"))
      (node (ref "IC1") (pin "W29") (pinfunction "DIGPRGND1_W29") (pintype "passive"))
      (node (ref "IC1") (pin "Y30") (pinfunction "DIGPRGND2_Y30") (pintype "passive"))
    )
    (net (code "2") (name "Net-(C42-Pad1)") (class "Default")
      (node (ref "C42") (pin "1") (pinfunction "1_1") (pintype "passive"))
      (node (ref "C43") (pin "1") (pinfunction "1_1") (pintype "passive"))
      (node (ref "IC1") (pin "AH30") (pinfunction "DIGPRVDD2_AH30") (pintype "passive"))
      (node (ref "R27") (pin "2") (pinfunction "2_2") (pintype "passive"))
    )
    (net (code "3") (name "Net-(C44-Pad1)") (class "Default")
      (node (ref "C44") (pin "1") (pinfunction "1_1") (pintype "passive"))
      (node (ref "C45") (pin "1") (pinfunction "1_1") (pintype "passive"))
      (node (ref "IC1") (pin "T32") (pinfunction "DIGPRVDD2_T32") (pintype "passive"))
      (node (ref "R23") (pin "2") (pinfunction "2_2") (pintype "passive"))
    )
    (net (code "4") (name "Net-(C46-Pad1)") (class "Default")
      (node (ref "C46") (pin "1") (pinfunction "1_1") (pintype "passive"))
      (node (ref "C47") (pin "1") (pinfunction "1_1") (pintype "passive"))
      (node (ref "IC1") (pin "AE29") (pinfunction "DIGPRVDD1_AE29") (pintype "passive"))
      (node (ref "R24") (pin "1") (pinfunction "1_1") (pintype "passive"))
    )
    (net (code "5") (name "Net-(C48-Pad1)") (class "Default")
      (node (ref "C48") (pin "1") (pinfunction "1_1") (pintype "passive"))
      (node (ref "C49") (pin "1") (pinfunction "1_1") (pintype "passive"))
      (node (ref "IC1") (pin "R31") (pinfunction "DIGPRVDD1_R31") (pintype "passive"))
      (node (ref "R20") (pin "1") (pinfunction "1_1") (pintype "passive"))
    )
    (net (code "6") (name "Net-(C52-Pad1)") (class "Default")
      (node (ref "C52") (pin "1") (pinfunction "1_1") (pintype "passive"))
      (node (ref "C53") (pin "1") (pinfunction "1_1") (pintype "passive"))
      (node (ref "IC1") (pin "H32") (pinfunction "DIGPRVDD2_H32") (pintype "passive"))
      (node (ref "R25") (pin "2") (pinfunction "2_2") (pintype "passive"))
    )
    (net (code "7") (name "Net-(C54-Pad1)") (class "Default")
      (node (ref "C54") (pin "1") (pinfunction "1_1") (pintype "passive"))
      (node (ref "C55") (pin "1") (pinfunction "1_1") (pintype "passive"))
      (node (ref "IC1") (pin "W33") (pinfunction "DIGPRVDD2_W33") (pintype "passive"))
      (node (ref "R21") (pin "2") (pinfunction "2_2") (pintype "passive"))
    )
    (net (code "8") (name "Net-(C56-Pad1)") (class "Default")
      (node (ref "C56") (pin "1") (pinfunction "1_1") (pintype "passive"))
      (node (ref "C57") (pin "1") (pinfunction "1_1") (pintype "passive"))
      (node (ref "IC1") (pin "AA29") (pinfunction "DIGPRVDD1_AA29") (pintype "passive"))
      (node (ref "R26") (pin "1") (pinfunction "1_1") (pintype "passive"))
    )
    (net (code "9") (name "Net-(C58-Pad1)") (class "Default")
      (node (ref "C58") (pin "1") (pinfunction "1_1") (pintype "passive"))
      (node (ref "C59") (pin "1") (pinfunction "1_1") (pintype "passive"))
      (node (ref "IC1") (pin "L33") (pinfunction "DIGPRVDD1_L33") (pintype "passive"))
      (node (ref "R22") (pin "1") (pinfunction "1_1") (pintype "passive"))
    )
    (net (code "10") (name "Net-(C72-Pad1)") (class "Default")
      (node (ref "C72") (pin "1") (pinfunction "1_1") (pintype "passive"))
      (node (ref "FR10") (pin "1") (pinfunction "1_1") (pintype "passive"))
      (node (ref "R31") (pin "1") (pinfunction "1_1") (pintype "passive"))
    )
    (net (code "11") (name "Net-(C85-Pad1)") (class "Default")
      (node (ref "C85") (pin "1") (pinfunction "1_1") (pintype "passive"))
      (node (ref "FR20") (pin "1") (pinfunction "1_1") (pintype "passive"))
      (node (ref "R37") (pin "1") (pinfunction "1_1") (pintype "passive"))
    )
    (net (code "12") (name "Net-(C94-Pad1)") (class "Default")
      (node (ref "C94") (pin "1") (pinfunction "1_1") (pintype "passive"))
      (node (ref "FR29") (pin "2") (pinfunction "2_2") (pintype "passive"))
      (node (ref "R38") (pin "2") (pinfunction "2_2") (pintype "passive"))
    )
    (net (code "13") (name "Net-(C96-Pad1)") (class "Default")
      (node (ref "C96") (pin "1") (pinfunction "1_1") (pintype "passive"))
      (node (ref "FR31") (pin "2") (pinfunction "2_2") (pintype "passive"))
      (node (ref "R39") (pin "2") (pinfunction "2_2") (pintype "passive"))
    )
    (net (code "14") (name "Net-(IC1B-DIGPRPOC)") (class "Default")
      (node (ref "C50") (pin "1") (pinfunction "1_1") (pintype "passive"))
      (node (ref "C51") (pin "1") (pinfunction "1_1") (pintype "passive"))
      (node (ref "IC1") (pin "W31") (pinfunction "DIGPRPOC_W31") (pintype "passive"))
      (node (ref "R28") (pin "2") (pinfunction "2_2") (pintype "passive"))
    )
    (net (code "15") (name "Net-(IC1B-DVDD_CGEN)") (class "Default")
      (node (ref "C73") (pin "1") (pinfunction "1_1") (pintype "passive"))
      (node (ref "FR11") (pin "1") (pinfunction "1_1") (pintype "passive"))
      (node (ref "IC1") (pin "A17") (pinfunction "DVDD_CGEN_A17") (pintype "passive"))
    )
    (net (code "16") (name "Net-(IC1B-DVDD_SXR)") (class "Default")
      (node (ref "C67") (pin "1") (pinfunction "1_1") (pintype "passive"))
      (node (ref "FR5") (pin "2") (pinfunction "2_2") (pintype "passive"))
      (node (ref "IC1") (pin "AL21") (pinfunction "DVDD_SXR_AL21") (pintype "passive"))
    )
    (net (code "17") (name "Net-(IC1B-DVDD_SXT)") (class "Default")
      (node (ref "C69") (pin "1") (pinfunction "1_1") (pintype "passive"))
      (node (ref "FR9") (pin "2") (pinfunction "2_2") (pintype "passive"))
      (node (ref "IC1") (pin "M4") (pinfunction "DVDD_SXT_M4") (pintype "passive"))
    )
    (net (code "18") (name "Net-(IC1B-VDD12O_VCO_SXT)") (class "Default")
      (node (ref "IC1") (pin "J5") (pinfunction "VDD12O_VCO_SXT_J5") (pintype "passive"))
      (node (ref "R32") (pin "1") (pinfunction "1_1") (pintype "passive"))
    )
    (net (code "19") (name "Net-(IC1B-VDD12_DIG)") (class "Default")
      (node (ref "C60") (pin "1") (pinfunction "1_1") (pintype "passive"))
      (node (ref "FR2") (pin "2") (pinfunction "2_2") (pintype "passive"))
      (node (ref "IC1") (pin "C25") (pinfunction "VDD12_DIG_C25") (pintype "passive"))
    )
    (net (code "20") (name "Net-(IC1B-VDD12_LNA_RFE)") (class "Default")
      (node (ref "C91") (pin "1") (pinfunction "1_1") (pintype "passive"))
      (node (ref "FR28") (pin "2") (pinfunction "2_2") (pintype "passive"))
      (node (ref "IC1") (pin "AG5") (pinfunction "VDD12_LNA_RFE_AG5") (pintype "passive"))
    )
    (net (code "21") (name "Net-(IC1B-VDD12_RXBUF)") (class "Default")
      (node (ref "C93") (pin "1") (pinfunction "1_1") (pintype "passive"))
      (node (ref "FR29") (pin "1") (pinfunction "1_1") (pintype "passive"))
      (node (ref "IC1") (pin "AP26") (pinfunction "VDD12_RXBUF_AP26") (pintype "passive"))
    )
    (net (code "22") (name "Net-(IC1B-VDD12_TIA_RFE)") (class "Default")
      (node (ref "C87") (pin "1") (pinfunction "1_1") (pintype "passive"))
      (node (ref "FR27") (pin "2") (pinfunction "2_2") (pintype "passive"))
      (node (ref "IC1") (pin "AD6") (pinfunction "VDD12_TIA_RFE_AD6") (pintype "passive"))
    )
    (net (code "23") (name "Net-(IC1B-VDD12_TXBUF)") (class "Default")
      (node (ref "C81") (pin "1") (pinfunction "1_1") (pintype "passive"))
      (node (ref "FR20") (pin "2") (pinfunction "2_2") (pintype "passive"))
      (node (ref "IC1") (pin "G5") (pinfunction "VDD12_TXBUF_G5") (pintype "passive"))
    )
    (net (code "24") (name "Net-(IC1B-VDD12_VCO_SXR)") (class "Default")
      (node (ref "C80") (pin "1") (pinfunction "1_1") (pintype "passive"))
      (node (ref "FR15") (pin "1") (pinfunction "1_1") (pintype "passive"))
      (node (ref "IC1") (pin "AN23") (pinfunction "VDD12_VCO_SXR_AN23") (pintype "passive"))
    )
    (net (code "25") (name "Net-(IC1B-VDD12_VCO_SXT)") (class "Default")
      (node (ref "C78") (pin "2") (pinfunction "2_2") (pintype "passive"))
      (node (ref "FR14") (pin "2") (pinfunction "2_2") (pintype "passive"))
      (node (ref "IC1") (pin "K6") (pinfunction "VDD12_VCO_SXT_K6") (pintype "passive"))
      (node (ref "R32") (pin "2") (pinfunction "2_2") (pintype "passive"))
    )
    (net (code "26") (name "Net-(IC1B-VDD14_LNA_RFE)") (class "Default")
      (node (ref "C98") (pin "1") (pinfunction "1_1") (pintype "passive"))
      (node (ref "FR33") (pin "1") (pinfunction "1_1") (pintype "passive"))
      (node (ref "IC1") (pin "AF6") (pinfunction "VDD14_LNA_RFE_AF6") (pintype "passive"))
    )
    (net (code "27") (name "Net-(IC1B-VDD14_RBB)") (class "Default")
      (node (ref "C99") (pin "1") (pinfunction "1_1") (pintype "passive"))
      (node (ref "FR34") (pin "1") (pinfunction "1_1") (pintype "passive"))
      (node (ref "IC1") (pin "AD4") (pinfunction "VDD14_RBB_AD4") (pintype "passive"))
    )
    (net (code "28") (name "Net-(IC1B-VDD14_TIA_RFE)") (class "Default")
      (node (ref "C100") (pin "1") (pinfunction "1_1") (pintype "passive"))
      (node (ref "FR35") (pin "1") (pinfunction "1_1") (pintype "passive"))
      (node (ref "IC1") (pin "AF2") (pinfunction "VDD14_TIA_RFE_AF2") (pintype "passive"))
    )
    (net (code "29") (name "Net-(IC1B-VDD14_VCO_CGEN)") (class "Default")
      (node (ref "C76") (pin "1") (pinfunction "1_1") (pintype "passive"))
      (node (ref "FR17") (pin "1") (pinfunction "1_1") (pintype "passive"))
      (node (ref "IC1") (pin "C21") (pinfunction "VDD14_VCO_CGEN_C21") (pintype "passive"))
    )
    (net (code "30") (name "Net-(IC1B-VDD18_BIAS)") (class "Default")
      (node (ref "C66") (pin "1") (pinfunction "1_1") (pintype "passive"))
      (node (ref "FR3") (pin "1") (pinfunction "1_1") (pintype "passive"))
      (node (ref "IC1") (pin "E17") (pinfunction "VDD18_BIAS_E17") (pintype "passive"))
    )
    (net (code "31") (name "Net-(IC1B-VDD18_DIG)") (class "Default")
      (node (ref "C61") (pin "1") (pinfunction "1_1") (pintype "passive"))
      (node (ref "IC1") (pin "D24") (pinfunction "VDD18_DIG_D24") (pintype "passive"))
      (node (ref "R29") (pin "1") (pinfunction "1_1") (pintype "passive"))
    )
    (net (code "32") (name "Net-(IC1B-VDD18_LDO_RX)") (class "Default")
      (node (ref "C88") (pin "1") (pinfunction "1_1") (pintype "passive"))
      (node (ref "FR23") (pin "2") (pinfunction "2_2") (pintype "passive"))
      (node (ref "IC1") (pin "AE3") (pinfunction "VDD18_TIA_RFE_AE3") (pintype "passive"))
      (node (ref "IC1") (pin "AF4") (pinfunction "VDD18_LDO_RX_AF4") (pintype "passive"))
    )
    (net (code "33") (name "Net-(IC1B-VDD18_LDO_TX)") (class "Default")
      (node (ref "C82") (pin "1") (pinfunction "1_1") (pintype "passive"))
      (node (ref "FR21") (pin "2") (pinfunction "2_2") (pintype "passive"))
      (node (ref "IC1") (pin "N1") (pinfunction "VDD18_LDO_TX_N1") (pintype "passive"))
    )
    (net (code "34") (name "Net-(IC1B-VDD18_RXBUF)") (class "Default")
      (node (ref "C95") (pin "1") (pinfunction "1_1") (pintype "passive"))
      (node (ref "FR31") (pin "1") (pinfunction "1_1") (pintype "passive"))
      (node (ref "IC1") (pin "AM26") (pinfunction "VDD18_RXBUF_AM26") (pintype "passive"))
    )
    (net (code "35") (name "Net-(IC1B-VDD18_SXR)") (class "Default")
      (node (ref "C83") (pin "1") (pinfunction "1_1") (pintype "passive"))
      (node (ref "FR19") (pin "1") (pinfunction "1_1") (pintype "passive"))
      (node (ref "IC1") (pin "AM18") (pinfunction "VDD18_SXR_AM18") (pintype "passive"))
    )
    (net (code "36") (name "Net-(IC1B-VDD18_TRF)") (class "Default")
      (node (ref "C65") (pin "1") (pinfunction "1_1") (pintype "passive"))
      (node (ref "FR6") (pin "1") (pinfunction "1_1") (pintype "passive"))
      (node (ref "IC1") (pin "D16") (pinfunction "VDD18_TRF_D16") (pintype "passive"))
    )
    (net (code "37") (name "Net-(IC1B-VDD18_TXBUF)") (class "Default")
      (node (ref "C70") (pin "1") (pinfunction "1_1") (pintype "passive"))
      (node (ref "FR10") (pin "2") (pinfunction "2_2") (pintype "passive"))
      (node (ref "IC1") (pin "H6") (pinfunction "VDD18_TXBUF_H6") (pintype "passive"))
    )
    (net (code "38") (name "Net-(IC1B-VDD18_VCO_CGEN)") (class "Default")
      (node (ref "C64") (pin "1") (pinfunction "1_1") (pintype "passive"))
      (node (ref "FR7") (pin "1") (pinfunction "1_1") (pintype "passive"))
      (node (ref "IC1") (pin "E21") (pinfunction "VDD18_VCO_CGEN_E21") (pintype "passive"))
    )
    (net (code "39") (name "Net-(IC1B-VDD18_VCO_SXR)") (class "Default")
      (node (ref "C97") (pin "1") (pinfunction "1_1") (pintype "passive"))
      (node (ref "FR32") (pin "1") (pinfunction "1_1") (pintype "passive"))
      (node (ref "IC1") (pin "AK22") (pinfunction "VDD18_VCO_SXR_AK22") (pintype "passive"))
    )
    (net (code "40") (name "Net-(IC1B-VDD18_VCO_SXT)") (class "Default")
      (node (ref "C68") (pin "1") (pinfunction "1_1") (pintype "passive"))
      (node (ref "FR12") (pin "1") (pinfunction "1_1") (pintype "passive"))
      (node (ref "IC1") (pin "G3") (pinfunction "VDD18_VCO_SXT_G3") (pintype "passive"))
    )
    (net (code "41") (name "Net-(IC1B-VDDO_DIV_SXT)") (class "Default")
      (node (ref "IC1") (pin "K2") (pinfunction "VDDO_DIV_SXT_K2") (pintype "passive"))
      (node (ref "R35") (pin "1") (pinfunction "1_1") (pintype "passive"))
    )
    (net (code "42") (name "Net-(IC1B-VDDO_TLOBUF_TRF)") (class "Default")
      (node (ref "IC1") (pin "D6") (pinfunction "VDDO_TLOBUF_TRF_D6") (pintype "passive"))
      (node (ref "R30") (pin "2") (pinfunction "2_2") (pintype "passive"))
    )
    (net (code "43") (name "Net-(IC1B-VDD_AFE)") (class "Default")
      (node (ref "C90") (pin "1") (pinfunction "1_1") (pintype "passive"))
      (node (ref "FR26") (pin "1") (pinfunction "1_1") (pintype "passive"))
      (node (ref "IC1") (pin "AJ25") (pinfunction "VDD_AFE_AJ25") (pintype "passive"))
    )
    (net (code "44") (name "Net-(IC1B-VDD_CP_CGEN)") (class "Default")
      (node (ref "C77") (pin "1") (pinfunction "1_1") (pintype "passive"))
      (node (ref "IC1") (pin "F20") (pinfunction "VDD_CP_CGEN_F20") (pintype "passive"))
      (node (ref "R33") (pin "2") (pinfunction "2_2") (pintype "passive"))
    )
    (net (code "45") (name "Net-(IC1B-VDD_CP_SXR)") (class "Default")
      (node (ref "C84") (pin "1") (pinfunction "1_1") (pintype "passive"))
      (node (ref "IC1") (pin "AL19") (pinfunction "VDD_CP_SXR_AL19") (pintype "passive"))
      (node (ref "R36") (pin "2") (pinfunction "2_2") (pintype "passive"))
    )
    (net (code "46") (name "Net-(IC1B-VDD_CP_SXT)") (class "Default")
      (node (ref "C75") (pin "1") (pinfunction "1_1") (pintype "passive"))
      (node (ref "IC1") (pin "J3") (pinfunction "VDD_CP_SXT_J3") (pintype "passive"))
      (node (ref "R34") (pin "1") (pinfunction "1_1") (pintype "passive"))
    )
    (net (code "47") (name "Net-(IC1B-VDD_DIV_CGEN)") (class "Default")
      (node (ref "C74") (pin "1") (pinfunction "1_1") (pintype "passive"))
      (node (ref "FR13") (pin "1") (pinfunction "1_1") (pintype "passive"))
      (node (ref "IC1") (pin "E19") (pinfunction "VDD_DIV_CGEN_E19") (pintype "passive"))
    )
    (net (code "48") (name "Net-(IC1B-VDD_DIV_SXR)") (class "Default")
      (node (ref "C86") (pin "1") (pinfunction "1_1") (pintype "passive"))
      (node (ref "FR22") (pin "1") (pinfunction "1_1") (pintype "passive"))
      (node (ref "IC1") (pin "AM20") (pinfunction "VDD_DIV_SXR_AM20") (pintype "passive"))
    )
    (net (code "49") (name "Net-(IC1B-VDD_DIV_SXT)") (class "Default")
      (node (ref "C79") (pin "1") (pinfunction "1_1") (pintype "passive"))
      (node (ref "FR16") (pin "2") (pinfunction "2_2") (pintype "passive"))
      (node (ref "FR18") (pin "2") (pinfunction "2_2") (pintype "passive"))
      (node (ref "IC1") (pin "L5") (pinfunction "VDD_DIV_SXT_L5") (pintype "passive"))
      (node (ref "R35") (pin "2") (pinfunction "2_2") (pintype "passive"))
    )
    (net (code "50") (name "Net-(IC1B-VDD_MXLOBUF_RFE)") (class "Default")
      (node (ref "C89") (pin "1") (pinfunction "1_1") (pintype "passive"))
      (node (ref "FR24") (pin "1") (pinfunction "1_1") (pintype "passive"))
      (node (ref "FR25") (pin "1") (pinfunction "1_1") (pintype "passive"))
      (node (ref "IC1") (pin "AN17") (pinfunction "VDD_MXLOBUF_RFE_AN17") (pintype "passive"))
    )
    (net (code "51") (name "Net-(IC1B-VDD_SPI_BUF)") (class "Default")
      (node (ref "C63") (pin "1") (pinfunction "1_1") (pintype "passive"))
      (node (ref "FR4") (pin "2") (pinfunction "2_2") (pintype "passive"))
      (node (ref "IC1") (pin "F24") (pinfunction "VDD_SPI_BUF_F24") (pintype "passive"))
    )
    (net (code "52") (name "Net-(IC1B-VDD_TBB)") (class "Default")
      (node (ref "C92") (pin "1") (pinfunction "1_1") (pintype "passive"))
      (node (ref "FR30") (pin "2") (pinfunction "2_2") (pintype "passive"))
      (node (ref "IC1") (pin "P4") (pinfunction "VDD_TBB_P4") (pintype "passive"))
    )
    (net (code "53") (name "Net-(IC1B-VDD_TLOBUF_TRF)") (class "Default")
      (node (ref "C62") (pin "1") (pinfunction "1_1") (pintype "passive"))
      (node (ref "FR1") (pin "1") (pinfunction "1_1") (pintype "passive"))
      (node (ref "IC1") (pin "F8") (pinfunction "VDD_TLOBUF_TRF_F8") (pintype "passive"))
      (node (ref "R30") (pin "1") (pinfunction "1_1") (pintype "passive"))
    )
    (net (code "54") (name "Net-(IC1B-VDD_TPAD_TRF)") (class "Default")
      (node (ref "C71") (pin "1") (pinfunction "1_1") (pintype "passive"))
      (node (ref "FR8") (pin "1") (pinfunction "1_1") (pintype "passive"))
      (node (ref "IC1") (pin "B16") (pinfunction "VDD_TPAD_TRF_B16") (pintype "passive"))
    )
    (net (code "55") (name "VCC1P4_LMS") (class "Default")
      (node (ref "FR16") (pin "1") (pinfunction "1_1") (pintype "passive"))
      (node (ref "FR17") (pin "2") (pinfunction "2_2") (pintype "passive"))
      (node (ref "FR24") (pin "2") (pinfunction "2_2") (pintype "passive"))
      (node (ref "FR33") (pin "2") (pinfunction "2_2") (pintype "passive"))
      (node (ref "FR34") (pin "2") (pinfunction "2_2") (pintype "passive"))
      (node (ref "FR35") (pin "2") (pinfunction "2_2") (pintype "passive"))
    )
    (net (code "56") (name "VCC1P8_LMS") (class "Default")
      (node (ref "FR12") (pin "2") (pinfunction "2_2") (pintype "passive"))
      (node (ref "FR19") (pin "2") (pinfunction "2_2") (pintype "passive"))
      (node (ref "FR21") (pin "1") (pinfunction "1_1") (pintype "passive"))
      (node (ref "FR23") (pin "1") (pinfunction "1_1") (pintype "passive"))
      (node (ref "FR3") (pin "2") (pinfunction "2_2") (pintype "passive"))
      (node (ref "FR32") (pin "2") (pinfunction "2_2") (pintype "passive"))
      (node (ref "FR6") (pin "2") (pinfunction "2_2") (pintype "passive"))
      (node (ref "FR7") (pin "2") (pinfunction "2_2") (pintype "passive"))
      (node (ref "R29") (pin "2") (pinfunction "2_2") (pintype "passive"))
      (node (ref "R31") (pin "2") (pinfunction "2_2") (pintype "passive"))
      (node (ref "R39") (pin "1") (pinfunction "1_1") (pintype "passive"))
    )
    (net (code "57") (name "VCC1P25_LMS") (class "Default")
      (node (ref "FR1") (pin "2") (pinfunction "2_2") (pintype "passive"))
      (node (ref "FR11") (pin "2") (pinfunction "2_2") (pintype "passive"))
      (node (ref "FR13") (pin "2") (pinfunction "2_2") (pintype "passive"))
      (node (ref "FR14") (pin "1") (pinfunction "1_1") (pintype "passive"))
      (node (ref "FR15") (pin "2") (pinfunction "2_2") (pintype "passive"))
      (node (ref "FR18") (pin "1") (pinfunction "1_1") (pintype "passive"))
      (node (ref "FR2") (pin "1") (pinfunction "1_1") (pintype "passive"))
      (node (ref "FR22") (pin "2") (pinfunction "2_2") (pintype "passive"))
      (node (ref "FR25") (pin "2") (pinfunction "2_2") (pintype "passive"))
      (node (ref "FR26") (pin "2") (pinfunction "2_2") (pintype "passive"))
      (node (ref "FR27") (pin "1") (pinfunction "1_1") (pintype "passive"))
      (node (ref "FR28") (pin "1") (pinfunction "1_1") (pintype "passive"))
      (node (ref "FR30") (pin "1") (pinfunction "1_1") (pintype "passive"))
      (node (ref "FR4") (pin "1") (pinfunction "1_1") (pintype "passive"))
      (node (ref "FR5") (pin "1") (pinfunction "1_1") (pintype "passive"))
      (node (ref "FR8") (pin "2") (pinfunction "2_2") (pintype "passive"))
      (node (ref "FR9") (pin "1") (pinfunction "1_1") (pintype "passive"))
      (node (ref "R33") (pin "1") (pinfunction "1_1") (pintype "passive"))
      (node (ref "R34") (pin "2") (pinfunction "2_2") (pintype "passive"))
      (node (ref "R36") (pin "1") (pinfunction "1_1") (pintype "passive"))
      (node (ref "R37") (pin "2") (pinfunction "2_2") (pintype "passive"))
      (node (ref "R38") (pin "1") (pinfunction "1_1") (pintype "passive"))
    )
    (net (code "58") (name "VCC1P25_LMS_DIG") (class "Default")
      (node (ref "R20") (pin "2") (pinfunction "2_2") (pintype "passive"))
      (node (ref "R22") (pin "2") (pinfunction "2_2") (pintype "passive"))
      (node (ref "R24") (pin "2") (pinfunction "2_2") (pintype "passive"))
      (node (ref "R26") (pin "2") (pinfunction "2_2") (pintype "passive"))
    )
    (net (code "59") (name "VDIO_LMS") (class "Default")
      (node (ref "R21") (pin "1") (pinfunction "1_1") (pintype "passive"))
      (node (ref "R23") (pin "1") (pinfunction "1_1") (pintype "passive"))
      (node (ref "R25") (pin "1") (pinfunction "1_1") (pintype "passive"))
      (node (ref "R27") (pin "1") (pinfunction "1_1") (pintype "passive"))
      (node (ref "R28") (pin "1") (pinfunction "1_1") (pintype "passive"))
    )
  )
)
